# ultra-violet-tooth-sensor-mk-3_3.net
KiCad netlist of a schematic drawn in EAGLE
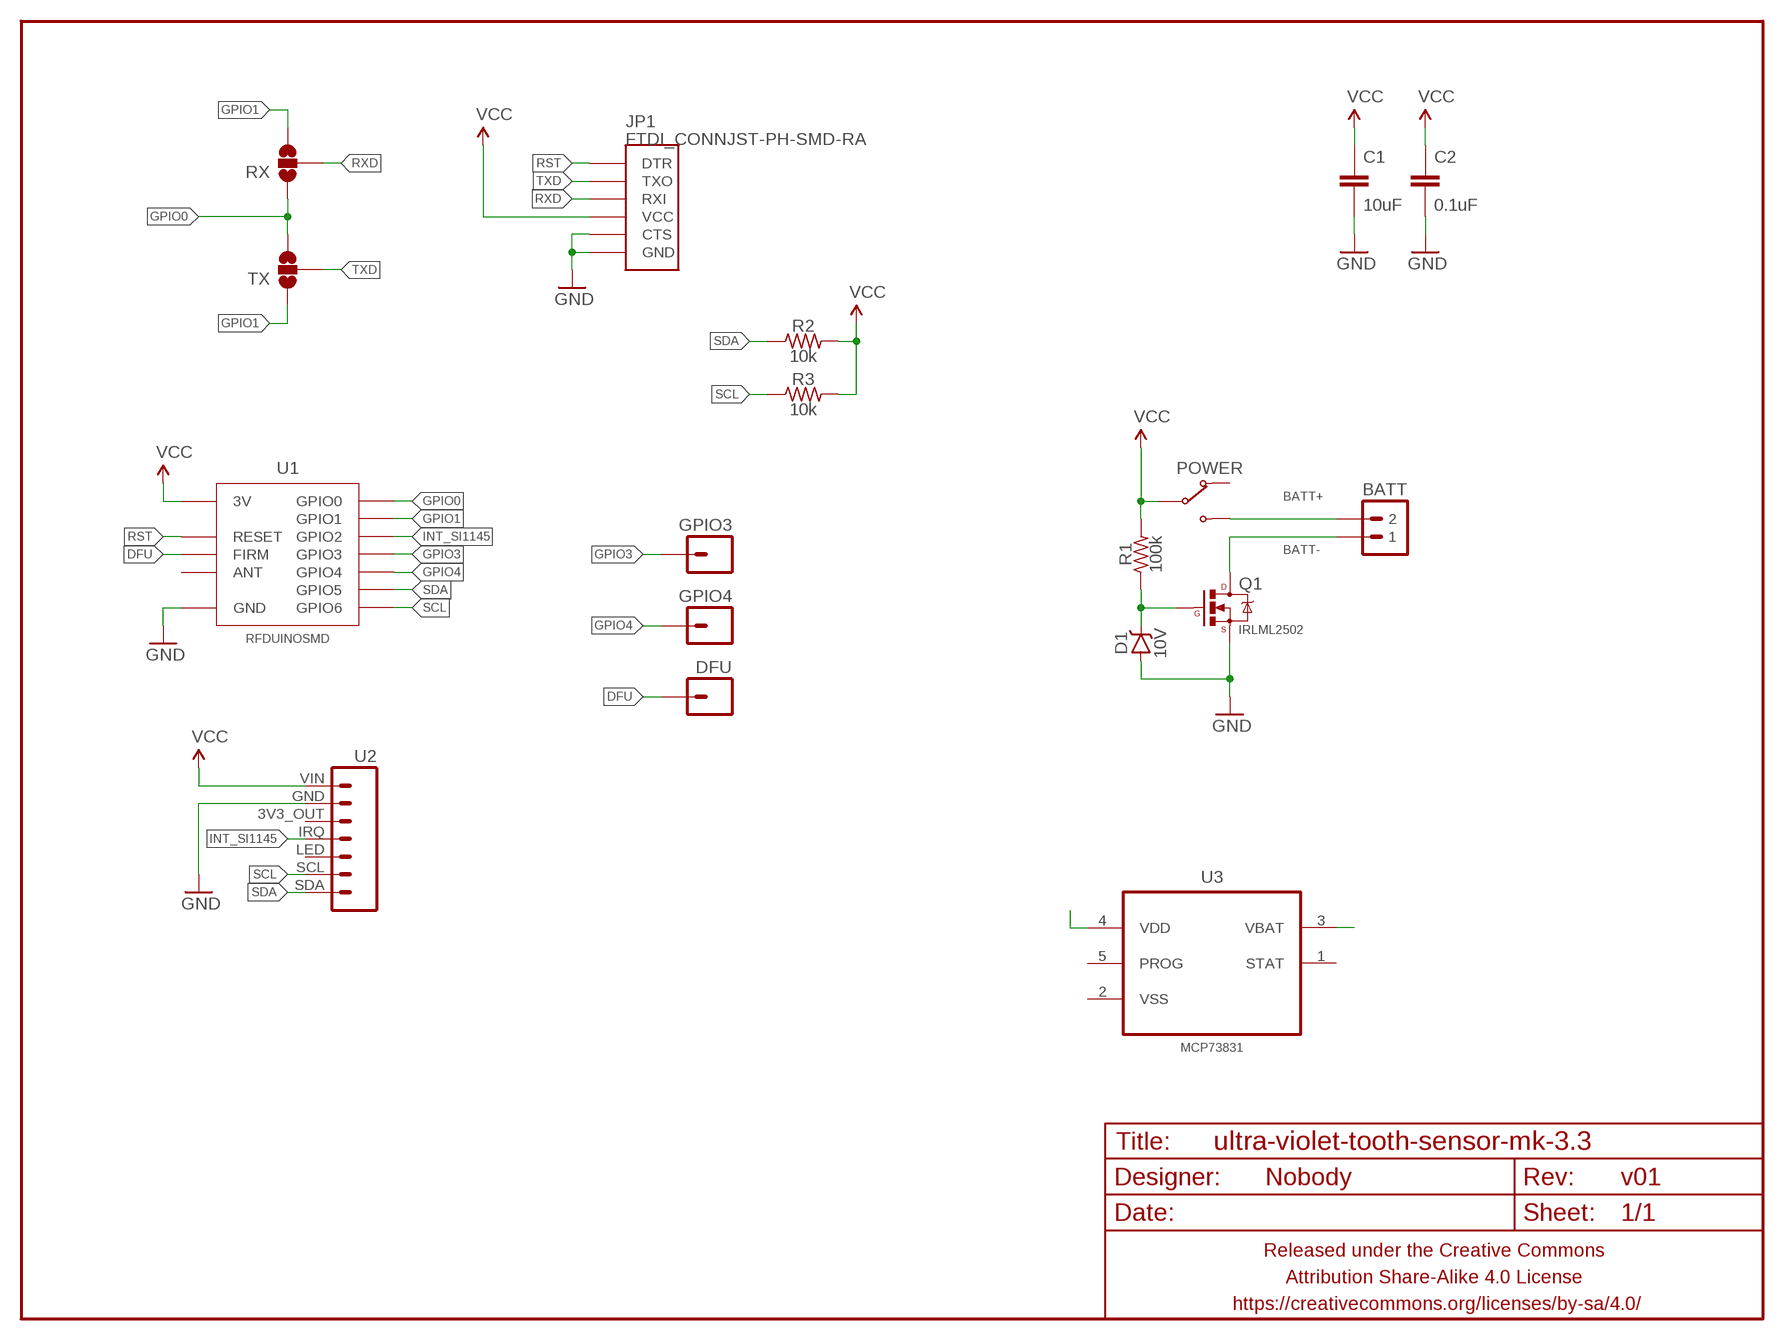
[diagram p0: schematic, sheet 1]

(export (version "E")
  (design (tool "Eeschema 10.0.6"))
  (components
    (comp (ref "BATT")
      (value "M02PTH-CENTERED-R+")
      (footprint "eagle-import:1X02-CENTER-R+")
      (libsource (lib "eagle-import") (part "M02PTH-CENTERED-R+"))
    )
    (comp (ref "C1")
      (value "10uF")
      (footprint "eagle-import:C1206")
      (libsource (lib "eagle-import") (part "CAPACITOR-CERAMICC1206"))
    )
    (comp (ref "C2")
      (value "0.1uF")
      (footprint "eagle-import:C0805")
      (libsource (lib "eagle-import") (part "CAPACITOR-CERAMICC0805"))
    )
    (comp (ref "D1")
      (value "10V")
      (footprint "eagle-import:SOT23")
      (libsource (lib "eagle-import") (part "DIODE-ZENERSOT23"))
    )
    (comp (ref "DFU")
      (value "M01SMD_1.5X2MM")
      (footprint "eagle-import:1X01_1.5X2MM")
      (libsource (lib "eagle-import") (part "M01SMD_1.5X2MM"))
    )
    (comp (ref "FRAME1")
      (value "FRAME-LETTERNO_PACKAGE")
      (footprint "eagle-import:DUMMY")
      (fields (field (name "DESIGNER") "Nobody"))
      (libsource (lib "eagle-import") (part "FRAME-LETTERNO_PACKAGE"))
    )
    (comp (ref "GPIO3")
      (value "M01SMD_1.5X2MM")
      (footprint "eagle-import:1X01_1.5X2MM")
      (libsource (lib "eagle-import") (part "M01SMD_1.5X2MM"))
    )
    (comp (ref "GPIO4")
      (value "M01SMD_1.5X2MM")
      (footprint "eagle-import:1X01_1.5X2MM")
      (libsource (lib "eagle-import") (part "M01SMD_1.5X2MM"))
    )
    (comp (ref "JP1")
      (value "FTDI_CONNJST-PH-SMD-RA")
      (footprint "eagle-import:AVRISP-JST-6-PH-RA-SMD")
      (libsource (lib "eagle-import") (part "FTDI_CONNJST-PH-SMD-RA"))
    )
    (comp (ref "POWER")
      (value "SWITCH-SPDTPTH-RA-2.54MM")
      (footprint "eagle-import:SPDT-RA-2.54MM")
      (libsource (lib "eagle-import") (part "SWITCH-SPDTPTH-RA-2.54MM"))
    )
    (comp (ref "Q1")
      (value "IRLML2502")
      (footprint "eagle-import:SOT23")
      (libsource (lib "eagle-import") (part "MOSFET-NCHANNELIRLML2502"))
    )
    (comp (ref "R1")
      (value "100k")
      (footprint "eagle-import:R0805")
      (libsource (lib "eagle-import") (part "RESISTORR0805"))
    )
    (comp (ref "R2")
      (value "10k")
      (footprint "eagle-import:R0805")
      (libsource (lib "eagle-import") (part "RESISTORR0805"))
    )
    (comp (ref "R3")
      (value "10k")
      (footprint "eagle-import:R0805")
      (libsource (lib "eagle-import") (part "RESISTORR0805"))
    )
    (comp (ref "RX")
      (value "JUMPER-PAD-3-NOFULL_BOX_SILK")
      (footprint "eagle-import:PAD-JUMPER-3-NO_YES_SILK_FULL_BOX")
      (libsource (lib "eagle-import") (part "JUMPER-PAD-3-NOFULL_BOX_SILK"))
    )
    (comp (ref "TX")
      (value "JUMPER-PAD-3-NOFULL_BOX_SILK")
      (footprint "eagle-import:PAD-JUMPER-3-NO_YES_SILK_FULL_BOX")
      (libsource (lib "eagle-import") (part "JUMPER-PAD-3-NOFULL_BOX_SILK"))
    )
    (comp (ref "U1")
      (value "RFDUINOSMD")
      (footprint "eagle-import:RFDUINO-SMD")
      (libsource (lib "eagle-import") (part "RFDUINOSMD"))
    )
    (comp (ref "U2")
      (value "ADAFRUIT-SI1145-BREAKOUTNOHOLEY")
      (footprint "eagle-import:ADAFRUIT-SI1145-BREAKOUT-NOHOLES")
      (libsource (lib "eagle-import") (part "ADAFRUIT-SI1145-BREAKOUTNOHOLEY"))
    )
    (comp (ref "U3")
      (value "MCP73831")
      (footprint "eagle-import:SOT95P280X145-5N")
      (fields (field (name "MPN") "MCP73831T-2ACI/OT"))
      (libsource (lib "eagle-import") (part "MCP73831T-2ACI/OT"))
    )
  )
  (nets
    (net (code "1") (name "/BATT+") (class "Default")
      (node (ref "BATT") (pin "2") (pinfunction "2_2") (pintype "passive"))
      (node (ref "POWER") (pin "3") (pinfunction "NO_3") (pintype "passive"))
    )
    (net (code "2") (name "/BATT-") (class "Default")
      (node (ref "BATT") (pin "1") (pinfunction "1_1") (pintype "passive"))
      (node (ref "Q1") (pin "3") (pinfunction "D_3") (pintype "passive"))
    )
    (net (code "3") (name "/VSS") (class "Default")
      (node (ref "U3") (pin "2") (pinfunction "VSS_2") (pintype "power_in"))
    )
    (net (code "4") (name "DFU") (class "Default")
      (node (ref "DFU") (pin "P$1") (pinfunction "1_P$1") (pintype "passive"))
      (node (ref "U1") (pin "FACTORY") (pinfunction "FIRM_FACTORY") (pintype "bidirectional"))
    )
    (net (code "5") (name "GND") (class "Default")
      (node (ref "C1") (pin "2") (pinfunction "2_2") (pintype "passive"))
      (node (ref "C2") (pin "2") (pinfunction "2_2") (pintype "passive"))
      (node (ref "D1") (pin "1") (pinfunction "A_1") (pintype "passive"))
      (node (ref "D1") (pin "2") (pinfunction "A_2") (pintype "passive"))
      (node (ref "JP1") (pin "CTS") (pinfunction "CTS_CTS") (pintype "bidirectional"))
      (node (ref "JP1") (pin "GND") (pinfunction "GND_GND") (pintype "bidirectional"))
      (node (ref "Q1") (pin "2") (pinfunction "S_2") (pintype "passive"))
      (node (ref "U1") (pin "GND@1") (pinfunction "GND_GND@1") (pintype "bidirectional"))
      (node (ref "U1") (pin "GND@2") (pinfunction "GND_GND@2") (pintype "bidirectional"))
      (node (ref "U1") (pin "GND@3") (pinfunction "GND_GND@3") (pintype "bidirectional"))
      (node (ref "U1") (pin "GND@4") (pinfunction "GND_GND@4") (pintype "bidirectional"))
      (node (ref "U1") (pin "GND@5") (pinfunction "GND_GND@5") (pintype "bidirectional"))
      (node (ref "U1") (pin "GND@6") (pinfunction "GND_GND@6") (pintype "bidirectional"))
      (node (ref "U1") (pin "GND@7") (pinfunction "GND_GND@7") (pintype "bidirectional"))
      (node (ref "U1") (pin "GND@8") (pinfunction "GND_GND@8") (pintype "bidirectional"))
      (node (ref "U2") (pin "GND") (pinfunction "GND_GND") (pintype "passive"))
    )
    (net (code "6") (name "GPIO0") (class "Default")
      (node (ref "RX") (pin "1") (pinfunction "1_1") (pintype "passive"))
      (node (ref "TX") (pin "3") (pinfunction "3_3") (pintype "passive"))
      (node (ref "U1") (pin "GPIO0") (pinfunction "GPIO0_GPIO0") (pintype "bidirectional"))
    )
    (net (code "7") (name "GPIO1") (class "Default")
      (node (ref "RX") (pin "3") (pinfunction "3_3") (pintype "passive"))
      (node (ref "TX") (pin "1") (pinfunction "1_1") (pintype "passive"))
      (node (ref "U1") (pin "GPIO1") (pinfunction "GPIO1_GPIO1") (pintype "bidirectional"))
    )
    (net (code "8") (name "GPIO3") (class "Default")
      (node (ref "GPIO3") (pin "P$1") (pinfunction "1_P$1") (pintype "passive"))
      (node (ref "U1") (pin "GPIO3") (pinfunction "GPIO3_GPIO3") (pintype "bidirectional"))
    )
    (net (code "9") (name "GPIO4") (class "Default")
      (node (ref "GPIO4") (pin "P$1") (pinfunction "1_P$1") (pintype "passive"))
      (node (ref "U1") (pin "GPIO4") (pinfunction "GPIO4_GPIO4") (pintype "bidirectional"))
    )
    (net (code "10") (name "INT_SI1145") (class "Default")
      (node (ref "U1") (pin "GPIO2") (pinfunction "GPIO2_GPIO2") (pintype "bidirectional"))
      (node (ref "U2") (pin "IRQ") (pinfunction "IRQ_IRQ") (pintype "passive"))
    )
    (net (code "11") (name "Net-(D1-C)") (class "Default")
      (node (ref "D1") (pin "3") (pinfunction "C_3") (pintype "passive"))
      (node (ref "Q1") (pin "1") (pinfunction "G_1") (pintype "passive"))
      (node (ref "R1") (pin "1") (pinfunction "1_1") (pintype "passive"))
    )
    (net (code "12") (name "RST") (class "Default")
      (node (ref "JP1") (pin "DTR") (pinfunction "DTR_DTR") (pintype "bidirectional"))
      (node (ref "U1") (pin "RESET") (pinfunction "RESET_RESET") (pintype "bidirectional"))
    )
    (net (code "13") (name "RXD") (class "Default")
      (node (ref "JP1") (pin "RXI") (pinfunction "RXI_RXI") (pintype "bidirectional"))
      (node (ref "RX") (pin "2") (pinfunction "2_2") (pintype "passive"))
    )
    (net (code "14") (name "SCL") (class "Default")
      (node (ref "R3") (pin "1") (pinfunction "1_1") (pintype "passive"))
      (node (ref "U1") (pin "GPIO6") (pinfunction "GPIO6_GPIO6") (pintype "bidirectional"))
      (node (ref "U2") (pin "SCL") (pinfunction "SCL_SCL") (pintype "passive"))
    )
    (net (code "15") (name "SDA") (class "Default")
      (node (ref "R2") (pin "1") (pinfunction "1_1") (pintype "passive"))
      (node (ref "U1") (pin "GPIO5") (pinfunction "GPIO5_GPIO5") (pintype "bidirectional"))
      (node (ref "U2") (pin "SDA") (pinfunction "SDA_SDA") (pintype "passive"))
    )
    (net (code "16") (name "TXD") (class "Default")
      (node (ref "JP1") (pin "TXO") (pinfunction "TXO_TXO") (pintype "bidirectional"))
      (node (ref "TX") (pin "2") (pinfunction "2_2") (pintype "passive"))
    )
    (net (code "17") (name "VCC") (class "Default")
      (node (ref "C1") (pin "1") (pinfunction "1_1") (pintype "passive"))
      (node (ref "C2") (pin "1") (pinfunction "1_1") (pintype "passive"))
      (node (ref "JP1") (pin "VCC") (pinfunction "VCC_VCC") (pintype "bidirectional"))
      (node (ref "POWER") (pin "2") (pinfunction "COM_2") (pintype "passive"))
      (node (ref "R1") (pin "2") (pinfunction "2_2") (pintype "passive"))
      (node (ref "R2") (pin "2") (pinfunction "2_2") (pintype "passive"))
      (node (ref "R3") (pin "2") (pinfunction "2_2") (pintype "passive"))
      (node (ref "U1") (pin "3V") (pinfunction "3V_3V") (pintype "bidirectional"))
      (node (ref "U2") (pin "VIN") (pinfunction "VIN_VIN") (pintype "passive"))
    )
    (net (code "18") (name "unconnected-(POWER-NC-Pad1)") (class "Default")
      (node (ref "POWER") (pin "1") (pinfunction "NC_1") (pintype "passive"))
    )
    (net (code "19") (name "unconnected-(U1-PadANT)") (class "Default")
      (node (ref "U1") (pin "ANT") (pinfunction "ANT_ANT") (pintype "bidirectional"))
    )
    (net (code "20") (name "unconnected-(U2-Pad3V3_OUT)") (class "Default")
      (node (ref "U2") (pin "3V3_OUT") (pinfunction "3V3_OUT_3V3_OUT") (pintype "passive"))
    )
    (net (code "21") (name "unconnected-(U2-PadLED)") (class "Default")
      (node (ref "U2") (pin "LED") (pinfunction "LED_LED") (pintype "passive"))
    )
    (net (code "22") (name "unconnected-(U3-PROG-Pad5)") (class "Default")
      (node (ref "U3") (pin "5") (pinfunction "PROG_5") (pintype "input"))
    )
    (net (code "23") (name "unconnected-(U3-STAT-Pad1)") (class "Default")
      (node (ref "U3") (pin "1") (pinfunction "STAT_1") (pintype "output"))
    )
    (net (code "24") (name "unconnected-(U3-VBAT-Pad3)") (class "Default")
      (node (ref "U3") (pin "3") (pinfunction "VBAT_3") (pintype "output"))
    )
    (net (code "25") (name "unconnected-(U3-VDD-Pad4)") (class "Default")
      (node (ref "U3") (pin "4") (pinfunction "VDD_4") (pintype "power_in"))
    )
  )
)
